# Order_100022604_2Layer_Green_1_6mm_HASL_.net
KiCad netlist of a schematic drawn in EAGLE
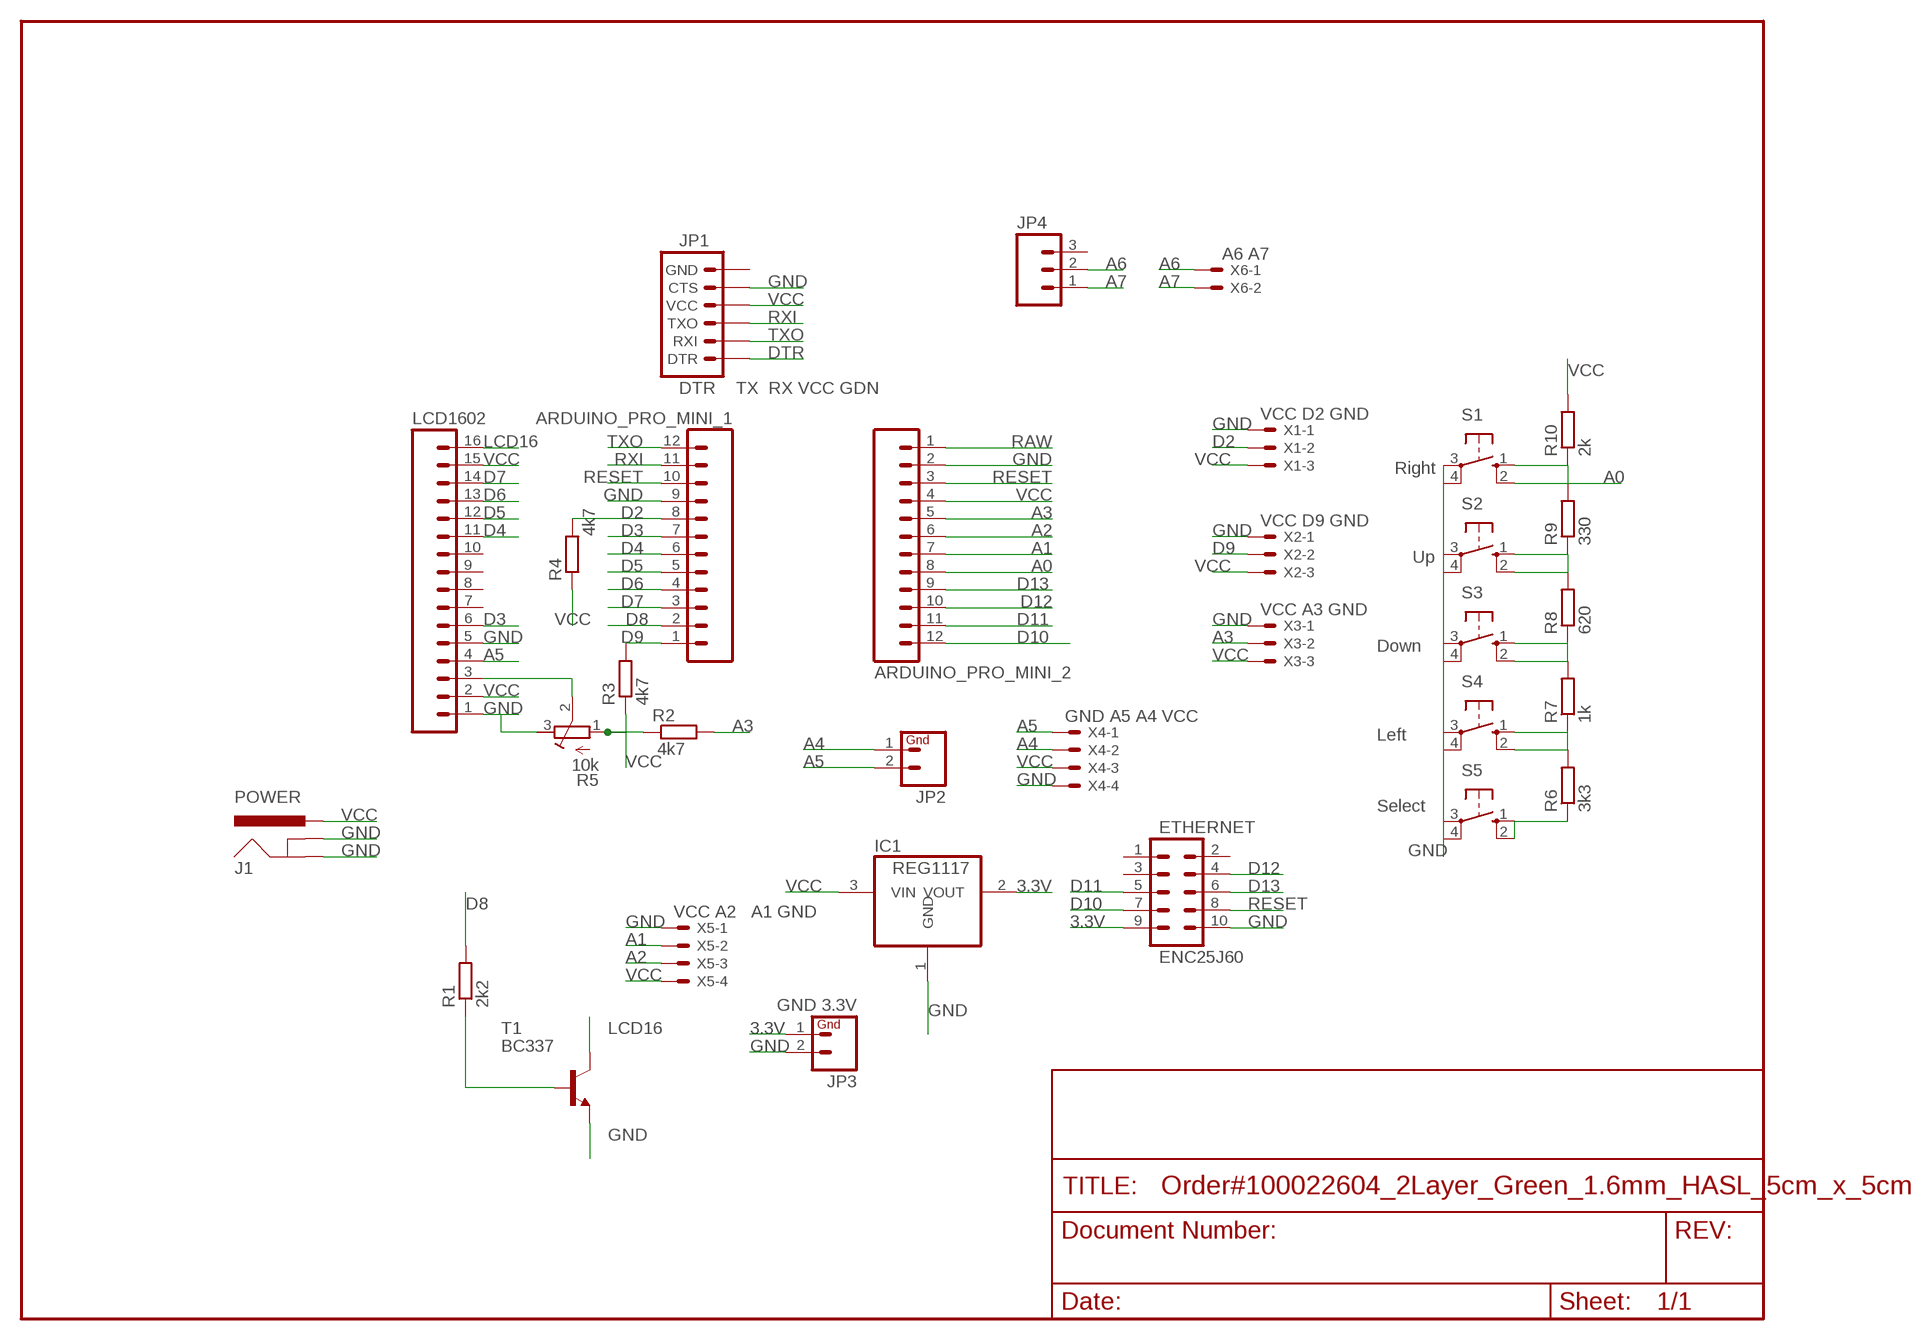
[diagram p0: schematic, sheet 1]

(export (version "E")
  (design (tool "Eeschema 10.0.6"))
  (components
    (comp (ref "ARDUINO_PRO_MINI_1")
      (value "M12PTH")
      (footprint "eagle-import:1X12")
      (libsource (lib "eagle-import") (part "M12PTH"))
    )
    (comp (ref "ARDUINO_PRO_MINI_2")
      (value "M12PTH")
      (footprint "eagle-import:1X12")
      (libsource (lib "eagle-import") (part "M12PTH"))
    )
    (comp (ref "ETHERNET")
      (value "ENC25J60")
      (footprint "eagle-import:AVR_ICSP")
      (libsource (lib "eagle-import") (part "M05X2PTH"))
    )
    (comp (ref "IC1")
      (value "REG1117")
      (footprint "eagle-import:SOT223")
      (libsource (lib "eagle-import") (part "REG1117"))
    )
    (comp (ref "J1")
      (value "POWER")
      (footprint "eagle-import:POWER_JACK_PTH_LOCK")
      (libsource (lib "eagle-import") (part "POWER_JACKPTH_LOCK"))
    )
    (comp (ref "JP1")
      (value "DTR TX RX VCC GDN")
      (footprint "eagle-import:1X06")
      (libsource (lib "eagle-import") (part "ARDUINO_SERIAL_PROGRAMPTH"))
    )
    (comp (ref "JP2")
      (value "M02PTH")
      (footprint "eagle-import:1X02")
      (libsource (lib "eagle-import") (part "M02PTH"))
    )
    (comp (ref "JP3")
      (value "GND 3.3V")
      (footprint "eagle-import:1X02")
      (libsource (lib "eagle-import") (part "M02PTH"))
    )
    (comp (ref "JP4")
      (value "M03PTH")
      (footprint "eagle-import:1X03")
      (libsource (lib "eagle-import") (part "M03PTH"))
    )
    (comp (ref "LCD1602")
      (value "HEADER-16P-2.54")
      (footprint "eagle-import:16P-2.54")
      (libsource (lib "eagle-import") (part "HEADER-16P-2.54"))
    )
    (comp (ref "R1")
      (value "2k2")
      (footprint "eagle-import:0207_10")
      (libsource (lib "eagle-import") (part "R-EU_0207/10"))
    )
    (comp (ref "R2")
      (value "4k7")
      (footprint "eagle-import:0207_10")
      (libsource (lib "eagle-import") (part "R-EU_0207/10"))
    )
    (comp (ref "R3")
      (value "4k7")
      (footprint "eagle-import:0207_10")
      (libsource (lib "eagle-import") (part "R-EU_0207/10"))
    )
    (comp (ref "R4")
      (value "4k7")
      (footprint "eagle-import:0207_10")
      (libsource (lib "eagle-import") (part "R-EU_0207/10"))
    )
    (comp (ref "R5")
      (value "10k")
      (footprint "eagle-import:RTRIM64W")
      (libsource (lib "eagle-import") (part "R-TRIMM64W"))
    )
    (comp (ref "R6")
      (value "3k3")
      (footprint "eagle-import:0207_10")
      (libsource (lib "eagle-import") (part "R-EU_0207/10"))
    )
    (comp (ref "R7")
      (value "1k")
      (footprint "eagle-import:0207_10")
      (libsource (lib "eagle-import") (part "R-EU_0207/10"))
    )
    (comp (ref "R8")
      (value "620")
      (footprint "eagle-import:0207_10")
      (libsource (lib "eagle-import") (part "R-EU_0207/10"))
    )
    (comp (ref "R9")
      (value "330")
      (footprint "eagle-import:0207_10")
      (libsource (lib "eagle-import") (part "R-EU_0207/10"))
    )
    (comp (ref "R10")
      (value "2k")
      (footprint "eagle-import:0207_10")
      (libsource (lib "eagle-import") (part "R-EU_0207/10"))
    )
    (comp (ref "S1")
      (value "Right")
      (footprint "eagle-import:B3F-10XX")
      (fields (field (name "MPN") "B3F-1000"))
      (libsource (lib "eagle-import") (part "10-XX"))
    )
    (comp (ref "S2")
      (value "Up")
      (footprint "eagle-import:B3F-10XX")
      (fields (field (name "MPN") "B3F-1000"))
      (libsource (lib "eagle-import") (part "10-XX"))
    )
    (comp (ref "S3")
      (value "Down")
      (footprint "eagle-import:B3F-10XX")
      (fields (field (name "MPN") "B3F-1000"))
      (libsource (lib "eagle-import") (part "10-XX"))
    )
    (comp (ref "S4")
      (value "Left")
      (footprint "eagle-import:B3F-10XX")
      (fields (field (name "MPN") "B3F-1000"))
      (libsource (lib "eagle-import") (part "10-XX"))
    )
    (comp (ref "S5")
      (value "Select")
      (footprint "eagle-import:B3F-10XX")
      (fields (field (name "MPN") "B3F-1000"))
      (libsource (lib "eagle-import") (part "10-XX"))
    )
    (comp (ref "T1")
      (value "BC337")
      (footprint "eagle-import:TO92")
      (libsource (lib "eagle-import") (part "BC337"))
    )
    (comp (ref "X1")
      (value "VCC D2 GND")
      (footprint "eagle-import:22-23-2031")
      (fields (field (name "MF") "MOLEX") (field (name "MPN") "22-23-2031"))
      (libsource (lib "eagle-import") (part "22-23-2031"))
    )
    (comp (ref "X2")
      (value "VCC D9 GND")
      (footprint "eagle-import:22-23-2031")
      (fields (field (name "MF") "MOLEX") (field (name "MPN") "22-23-2031"))
      (libsource (lib "eagle-import") (part "22-23-2031"))
    )
    (comp (ref "X3")
      (value "VCC A3 GND")
      (footprint "eagle-import:22-23-2031")
      (fields (field (name "MF") "MOLEX") (field (name "MPN") "22-23-2031"))
      (libsource (lib "eagle-import") (part "22-23-2031"))
    )
    (comp (ref "X4")
      (value "GND A5 A4 VCC")
      (footprint "eagle-import:22-23-2041")
      (fields (field (name "MF") "MOLEX") (field (name "MPN") "22-23-2041"))
      (libsource (lib "eagle-import") (part "22-23-2041"))
    )
    (comp (ref "X5")
      (value "VCC A2 A1 GND")
      (footprint "eagle-import:22-23-2041")
      (fields (field (name "MF") "MOLEX") (field (name "MPN") "22-23-2041"))
      (libsource (lib "eagle-import") (part "22-23-2041"))
    )
    (comp (ref "X6")
      (value "A6 A7")
      (footprint "eagle-import:22-23-2021")
      (fields (field (name "MF") "MOLEX") (field (name "MPN") "22-23-2021"))
      (libsource (lib "eagle-import") (part "22-23-2021"))
    )
  )
  (nets
    (net (code "1") (name "/3.3V") (class "Default")
      (node (ref "ETHERNET") (pin "9") (pinfunction "9_9") (pintype "passive"))
      (node (ref "IC1") (pin "2") (pinfunction "VOUT_2") (pintype "output"))
      (node (ref "JP3") (pin "1") (pinfunction "1_1") (pintype "passive"))
    )
    (net (code "2") (name "/A0") (class "Default")
      (node (ref "ARDUINO_PRO_MINI_2") (pin "8") (pinfunction "8_8") (pintype "passive"))
      (node (ref "R10") (pin "1") (pinfunction "1_1") (pintype "passive"))
      (node (ref "R9") (pin "2") (pinfunction "2_2") (pintype "passive"))
      (node (ref "S1") (pin "1") (pinfunction "S_1") (pintype "passive"))
      (node (ref "S1") (pin "2") (pinfunction "S1_2") (pintype "passive"))
    )
    (net (code "3") (name "/A1") (class "Default")
      (node (ref "ARDUINO_PRO_MINI_2") (pin "7") (pinfunction "7_7") (pintype "passive"))
      (node (ref "X5") (pin "2") (pinfunction "S_2") (pintype "passive"))
    )
    (net (code "4") (name "/A2") (class "Default")
      (node (ref "ARDUINO_PRO_MINI_2") (pin "6") (pinfunction "6_6") (pintype "passive"))
      (node (ref "X5") (pin "3") (pinfunction "S_3") (pintype "passive"))
    )
    (net (code "5") (name "/A3") (class "Default")
      (node (ref "ARDUINO_PRO_MINI_2") (pin "5") (pinfunction "5_5") (pintype "passive"))
      (node (ref "R2") (pin "2") (pinfunction "2_2") (pintype "passive"))
      (node (ref "X3") (pin "2") (pinfunction "S_2") (pintype "passive"))
    )
    (net (code "6") (name "/A4") (class "Default")
      (node (ref "JP2") (pin "1") (pinfunction "1_1") (pintype "passive"))
      (node (ref "X4") (pin "2") (pinfunction "S_2") (pintype "passive"))
    )
    (net (code "7") (name "/A5") (class "Default")
      (node (ref "JP2") (pin "2") (pinfunction "2_2") (pintype "passive"))
      (node (ref "LCD1602") (pin "4") (pinfunction "4_4") (pintype "passive"))
      (node (ref "X4") (pin "1") (pinfunction "S_1") (pintype "passive"))
    )
    (net (code "8") (name "/A6") (class "Default")
      (node (ref "JP4") (pin "2") (pinfunction "2_2") (pintype "passive"))
      (node (ref "X6") (pin "1") (pinfunction "S_1") (pintype "passive"))
    )
    (net (code "9") (name "/A7") (class "Default")
      (node (ref "JP4") (pin "1") (pinfunction "1_1") (pintype "passive"))
      (node (ref "X6") (pin "2") (pinfunction "S_2") (pintype "passive"))
    )
    (net (code "10") (name "/D2") (class "Default")
      (node (ref "ARDUINO_PRO_MINI_1") (pin "8") (pinfunction "8_8") (pintype "passive"))
      (node (ref "R4") (pin "2") (pinfunction "2_2") (pintype "passive"))
      (node (ref "X1") (pin "2") (pinfunction "S_2") (pintype "passive"))
    )
    (net (code "11") (name "/D3") (class "Default")
      (node (ref "ARDUINO_PRO_MINI_1") (pin "7") (pinfunction "7_7") (pintype "passive"))
      (node (ref "LCD1602") (pin "6") (pinfunction "6_6") (pintype "passive"))
    )
    (net (code "12") (name "/D4") (class "Default")
      (node (ref "ARDUINO_PRO_MINI_1") (pin "6") (pinfunction "6_6") (pintype "passive"))
      (node (ref "LCD1602") (pin "11") (pinfunction "11_11") (pintype "passive"))
    )
    (net (code "13") (name "/D5") (class "Default")
      (node (ref "ARDUINO_PRO_MINI_1") (pin "5") (pinfunction "5_5") (pintype "passive"))
      (node (ref "LCD1602") (pin "12") (pinfunction "12_12") (pintype "passive"))
    )
    (net (code "14") (name "/D6") (class "Default")
      (node (ref "ARDUINO_PRO_MINI_1") (pin "4") (pinfunction "4_4") (pintype "passive"))
      (node (ref "LCD1602") (pin "13") (pinfunction "13_13") (pintype "passive"))
    )
    (net (code "15") (name "/D7") (class "Default")
      (node (ref "ARDUINO_PRO_MINI_1") (pin "3") (pinfunction "3_3") (pintype "passive"))
      (node (ref "LCD1602") (pin "14") (pinfunction "14_14") (pintype "passive"))
    )
    (net (code "16") (name "/D8") (class "Default")
      (node (ref "ARDUINO_PRO_MINI_1") (pin "2") (pinfunction "2_2") (pintype "passive"))
      (node (ref "R1") (pin "2") (pinfunction "2_2") (pintype "passive"))
    )
    (net (code "17") (name "/D9") (class "Default")
      (node (ref "ARDUINO_PRO_MINI_1") (pin "1") (pinfunction "1_1") (pintype "passive"))
      (node (ref "R3") (pin "2") (pinfunction "2_2") (pintype "passive"))
      (node (ref "X2") (pin "2") (pinfunction "S_2") (pintype "passive"))
    )
    (net (code "18") (name "/D10") (class "Default")
      (node (ref "ARDUINO_PRO_MINI_2") (pin "12") (pinfunction "12_12") (pintype "passive"))
      (node (ref "ETHERNET") (pin "7") (pinfunction "7_7") (pintype "passive"))
    )
    (net (code "19") (name "/D11") (class "Default")
      (node (ref "ARDUINO_PRO_MINI_2") (pin "11") (pinfunction "11_11") (pintype "passive"))
      (node (ref "ETHERNET") (pin "5") (pinfunction "5_5") (pintype "passive"))
    )
    (net (code "20") (name "/D12") (class "Default")
      (node (ref "ARDUINO_PRO_MINI_2") (pin "10") (pinfunction "10_10") (pintype "passive"))
      (node (ref "ETHERNET") (pin "4") (pinfunction "4_4") (pintype "passive"))
    )
    (net (code "21") (name "/D13") (class "Default")
      (node (ref "ARDUINO_PRO_MINI_2") (pin "9") (pinfunction "9_9") (pintype "passive"))
      (node (ref "ETHERNET") (pin "6") (pinfunction "6_6") (pintype "passive"))
    )
    (net (code "22") (name "/DTR") (class "Default")
      (node (ref "JP1") (pin "1") (pinfunction "DTR_1") (pintype "passive"))
    )
    (net (code "23") (name "/GND") (class "Default")
      (node (ref "ARDUINO_PRO_MINI_1") (pin "9") (pinfunction "9_9") (pintype "passive"))
      (node (ref "ARDUINO_PRO_MINI_2") (pin "2") (pinfunction "2_2") (pintype "passive"))
      (node (ref "ETHERNET") (pin "10") (pinfunction "10_10") (pintype "passive"))
      (node (ref "IC1") (pin "1") (pinfunction "GND_1") (pintype "power_in"))
      (node (ref "J1") (pin "GND") (pinfunction "GND_GND") (pintype "bidirectional"))
      (node (ref "J1") (pin "GNDBREAK") (pinfunction "GNDBREAK_GNDBREAK") (pintype "bidirectional"))
      (node (ref "JP1") (pin "5") (pinfunction "CTS_5") (pintype "passive"))
      (node (ref "JP3") (pin "2") (pinfunction "2_2") (pintype "passive"))
      (node (ref "LCD1602") (pin "1") (pinfunction "1_1") (pintype "passive"))
      (node (ref "LCD1602") (pin "5") (pinfunction "5_5") (pintype "passive"))
      (node (ref "R5") (pin "3") (pinfunction "A_3") (pintype "passive"))
      (node (ref "S1") (pin "3") (pinfunction "P_3") (pintype "passive"))
      (node (ref "S1") (pin "4") (pinfunction "P1_4") (pintype "passive"))
      (node (ref "S2") (pin "3") (pinfunction "P_3") (pintype "passive"))
      (node (ref "S2") (pin "4") (pinfunction "P1_4") (pintype "passive"))
      (node (ref "S3") (pin "3") (pinfunction "P_3") (pintype "passive"))
      (node (ref "S3") (pin "4") (pinfunction "P1_4") (pintype "passive"))
      (node (ref "S4") (pin "3") (pinfunction "P_3") (pintype "passive"))
      (node (ref "S4") (pin "4") (pinfunction "P1_4") (pintype "passive"))
      (node (ref "S5") (pin "3") (pinfunction "P_3") (pintype "passive"))
      (node (ref "S5") (pin "4") (pinfunction "P1_4") (pintype "passive"))
      (node (ref "T1") (pin "1") (pinfunction "E_1") (pintype "passive"))
      (node (ref "X1") (pin "1") (pinfunction "S_1") (pintype "passive"))
      (node (ref "X2") (pin "1") (pinfunction "S_1") (pintype "passive"))
      (node (ref "X3") (pin "1") (pinfunction "S_1") (pintype "passive"))
      (node (ref "X4") (pin "4") (pinfunction "S_4") (pintype "passive"))
      (node (ref "X5") (pin "1") (pinfunction "S_1") (pintype "passive"))
    )
    (net (code "24") (name "/LCD16") (class "Default")
      (node (ref "LCD1602") (pin "16") (pinfunction "16_16") (pintype "passive"))
      (node (ref "T1") (pin "3") (pinfunction "C_3") (pintype "passive"))
    )
    (net (code "25") (name "/RAW") (class "Default")
      (node (ref "ARDUINO_PRO_MINI_2") (pin "1") (pinfunction "1_1") (pintype "passive"))
    )
    (net (code "26") (name "/RESET") (class "Default")
      (node (ref "ARDUINO_PRO_MINI_1") (pin "10") (pinfunction "10_10") (pintype "passive"))
      (node (ref "ARDUINO_PRO_MINI_2") (pin "3") (pinfunction "3_3") (pintype "passive"))
      (node (ref "ETHERNET") (pin "8") (pinfunction "8_8") (pintype "passive"))
    )
    (net (code "27") (name "/RXI") (class "Default")
      (node (ref "ARDUINO_PRO_MINI_1") (pin "11") (pinfunction "11_11") (pintype "passive"))
      (node (ref "JP1") (pin "3") (pinfunction "TXO_3") (pintype "passive"))
    )
    (net (code "28") (name "/TXO") (class "Default")
      (node (ref "ARDUINO_PRO_MINI_1") (pin "12") (pinfunction "12_12") (pintype "passive"))
      (node (ref "JP1") (pin "2") (pinfunction "RXI_2") (pintype "passive"))
    )
    (net (code "29") (name "/VCC") (class "Default")
      (node (ref "ARDUINO_PRO_MINI_2") (pin "4") (pinfunction "4_4") (pintype "passive"))
      (node (ref "IC1") (pin "3") (pinfunction "VIN_3") (pintype "input"))
      (node (ref "J1") (pin "PWR") (pinfunction "PWR_PWR") (pintype "bidirectional"))
      (node (ref "JP1") (pin "4") (pinfunction "VCC_4") (pintype "passive"))
      (node (ref "LCD1602") (pin "15") (pinfunction "15_15") (pintype "passive"))
      (node (ref "LCD1602") (pin "2") (pinfunction "2_2") (pintype "passive"))
      (node (ref "R10") (pin "2") (pinfunction "2_2") (pintype "passive"))
      (node (ref "R2") (pin "1") (pinfunction "1_1") (pintype "passive"))
      (node (ref "R3") (pin "1") (pinfunction "1_1") (pintype "passive"))
      (node (ref "R4") (pin "1") (pinfunction "1_1") (pintype "passive"))
      (node (ref "R5") (pin "1") (pinfunction "E_1") (pintype "passive"))
      (node (ref "X1") (pin "3") (pinfunction "S_3") (pintype "passive"))
      (node (ref "X2") (pin "3") (pinfunction "S_3") (pintype "passive"))
      (node (ref "X3") (pin "3") (pinfunction "S_3") (pintype "passive"))
      (node (ref "X4") (pin "3") (pinfunction "S_3") (pintype "passive"))
      (node (ref "X5") (pin "4") (pinfunction "S_4") (pintype "passive"))
    )
    (net (code "30") (name "Net-(R5-S)") (class "Default")
      (node (ref "LCD1602") (pin "3") (pinfunction "3_3") (pintype "passive"))
      (node (ref "R5") (pin "2") (pinfunction "S_2") (pintype "passive"))
    )
    (net (code "31") (name "Net-(S2-S)") (class "Default")
      (node (ref "R8") (pin "2") (pinfunction "2_2") (pintype "passive"))
      (node (ref "R9") (pin "1") (pinfunction "1_1") (pintype "passive"))
      (node (ref "S2") (pin "1") (pinfunction "S_1") (pintype "passive"))
      (node (ref "S2") (pin "2") (pinfunction "S1_2") (pintype "passive"))
    )
    (net (code "32") (name "Net-(S3-S)") (class "Default")
      (node (ref "R7") (pin "2") (pinfunction "2_2") (pintype "passive"))
      (node (ref "R8") (pin "1") (pinfunction "1_1") (pintype "passive"))
      (node (ref "S3") (pin "1") (pinfunction "S_1") (pintype "passive"))
      (node (ref "S3") (pin "2") (pinfunction "S1_2") (pintype "passive"))
    )
    (net (code "33") (name "Net-(S4-S)") (class "Default")
      (node (ref "R6") (pin "2") (pinfunction "2_2") (pintype "passive"))
      (node (ref "R7") (pin "1") (pinfunction "1_1") (pintype "passive"))
      (node (ref "S4") (pin "1") (pinfunction "S_1") (pintype "passive"))
      (node (ref "S4") (pin "2") (pinfunction "S1_2") (pintype "passive"))
    )
    (net (code "34") (name "Net-(S5-S)") (class "Default")
      (node (ref "R6") (pin "1") (pinfunction "1_1") (pintype "passive"))
      (node (ref "S5") (pin "1") (pinfunction "S_1") (pintype "passive"))
      (node (ref "S5") (pin "2") (pinfunction "S1_2") (pintype "passive"))
    )
    (net (code "35") (name "Net-(T1-B)") (class "Default")
      (node (ref "R1") (pin "1") (pinfunction "1_1") (pintype "passive"))
      (node (ref "T1") (pin "2") (pinfunction "B_2") (pintype "passive"))
    )
    (net (code "36") (name "unconnected-(ETHERNET-Pad1)") (class "Default")
      (node (ref "ETHERNET") (pin "1") (pinfunction "1_1") (pintype "passive"))
    )
    (net (code "37") (name "unconnected-(ETHERNET-Pad2)") (class "Default")
      (node (ref "ETHERNET") (pin "2") (pinfunction "2_2") (pintype "passive"))
    )
    (net (code "38") (name "unconnected-(ETHERNET-Pad3)") (class "Default")
      (node (ref "ETHERNET") (pin "3") (pinfunction "3_3") (pintype "passive"))
    )
    (net (code "39") (name "unconnected-(JP1-GND-Pad6)") (class "Default")
      (node (ref "JP1") (pin "6") (pinfunction "GND_6") (pintype "passive"))
    )
    (net (code "40") (name "unconnected-(JP4-Pad3)") (class "Default")
      (node (ref "JP4") (pin "3") (pinfunction "3_3") (pintype "passive"))
    )
    (net (code "41") (name "unconnected-(LCD1602-Pad7)") (class "Default")
      (node (ref "LCD1602") (pin "7") (pinfunction "7_7") (pintype "passive"))
    )
    (net (code "42") (name "unconnected-(LCD1602-Pad8)") (class "Default")
      (node (ref "LCD1602") (pin "8") (pinfunction "8_8") (pintype "passive"))
    )
    (net (code "43") (name "unconnected-(LCD1602-Pad9)") (class "Default")
      (node (ref "LCD1602") (pin "9") (pinfunction "9_9") (pintype "passive"))
    )
    (net (code "44") (name "unconnected-(LCD1602-Pad10)") (class "Default")
      (node (ref "LCD1602") (pin "10") (pinfunction "10_10") (pintype "passive"))
    )
  )
)
